# 2_Sheet_2_copy.net
KiCad netlist of a schematic drawn in Altium Designer
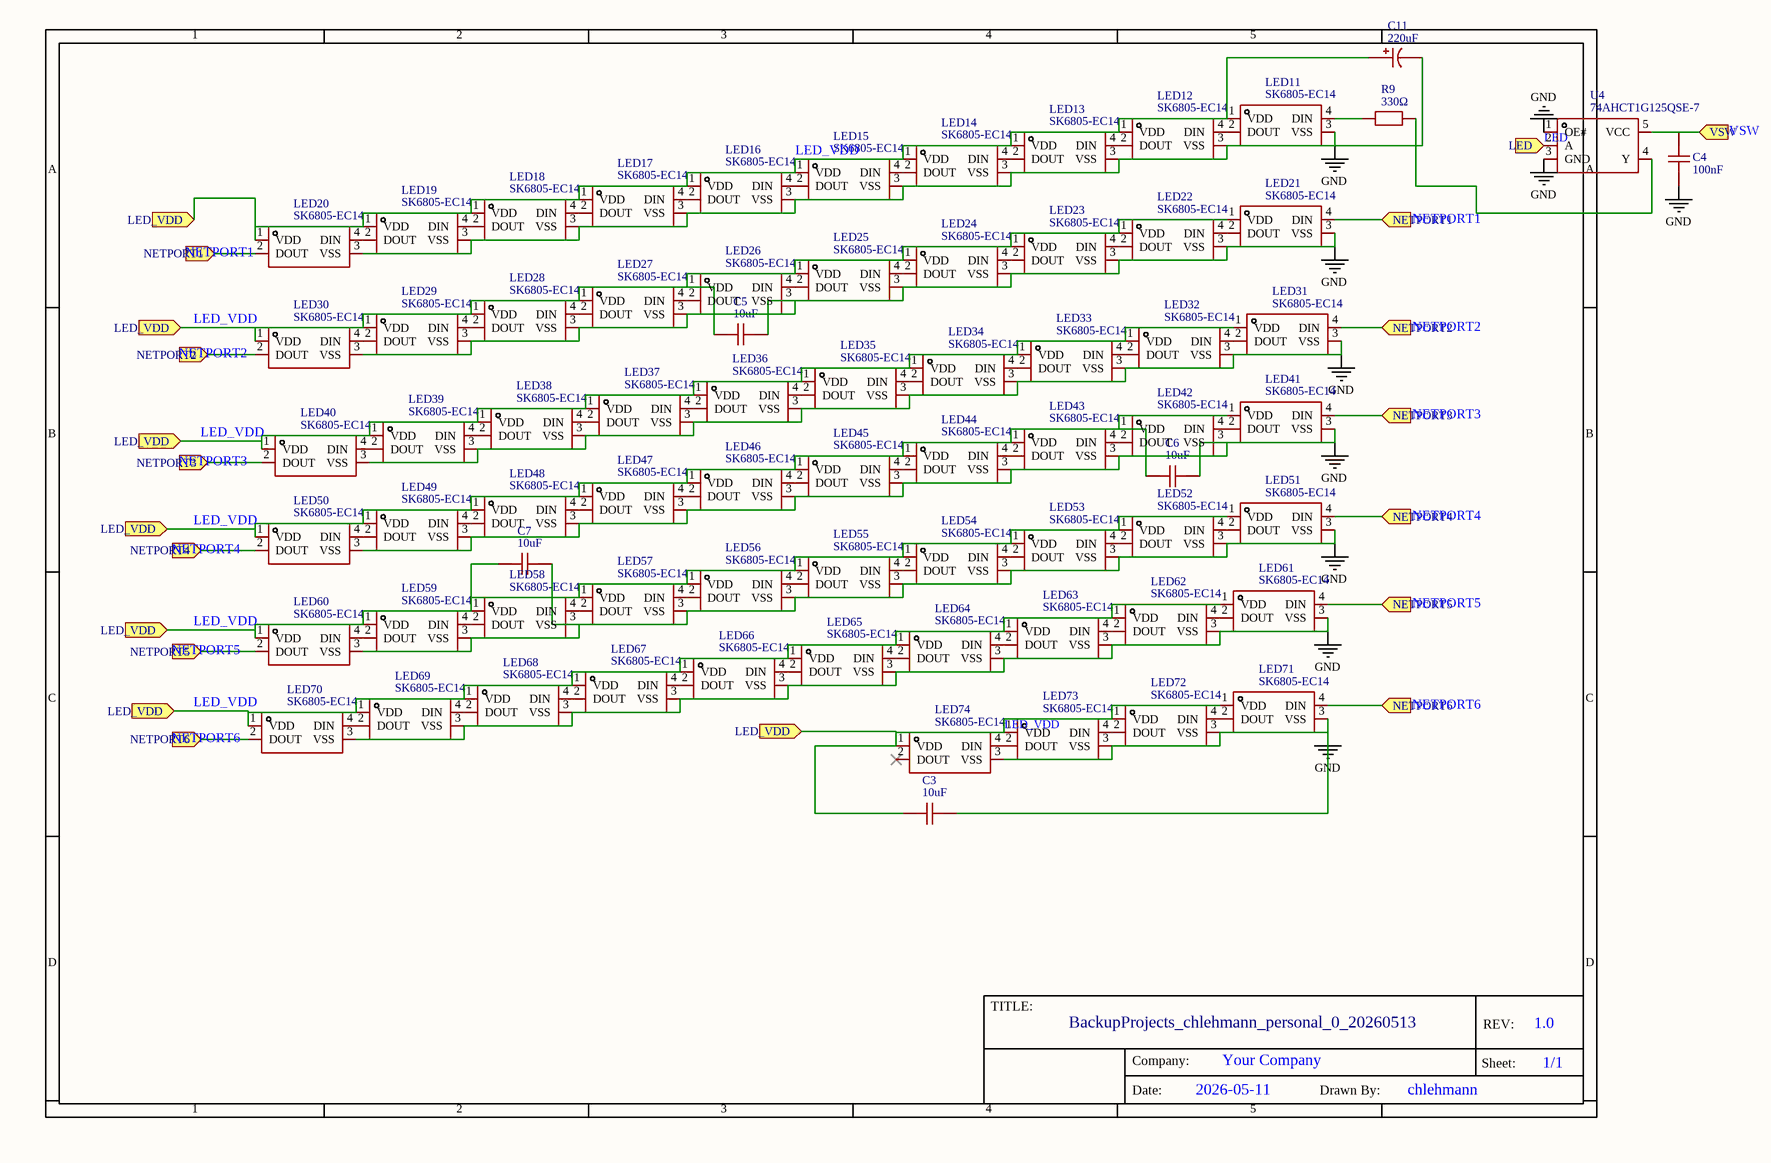
[diagram p0: 2_Sheet_2 copy.schdoc]

(export (version "E")
  (design (tool "Eeschema 10.0.6"))
  (components
    (comp (ref "C3")
      (value "10uF")
      (footprint "C0603")
      (fields
        (field (name "MANUFACTURER") "SAMSUNG(三星)")
        (field (name "MANUFACTURER PART") "CL10A106KP8NNNC")
      )
      (libsource (lib "altium-import") (part "root_0_10uF_"))
    )
    (comp (ref "C4")
      (value "100nF")
      (footprint "C0603")
      (fields
        (field (name "MANUFACTURER") "HRE(芯声)")
        (field (name "MANUFACTURER PART") "CGA0603X7R104K250JT")
        (field (name "CONTRIBUTOR") "lcsc")
      )
      (libsource (lib "altium-import") (part "root_1_100nF_"))
    )
    (comp (ref "C5")
      (value "10uF")
      (footprint "C0603")
      (fields
        (field (name "MANUFACTURER") "SAMSUNG(三星)")
        (field (name "MANUFACTURER PART") "CL10A106KP8NNNC")
      )
      (libsource (lib "altium-import") (part "root_0_10uF_"))
    )
    (comp (ref "C6")
      (value "10uF")
      (footprint "C0603")
      (fields
        (field (name "MANUFACTURER") "SAMSUNG(三星)")
        (field (name "MANUFACTURER PART") "CL10A106KP8NNNC")
      )
      (libsource (lib "altium-import") (part "root_0_10uF_"))
    )
    (comp (ref "C7")
      (value "10uF")
      (footprint "C0603")
      (fields
        (field (name "MANUFACTURER") "SAMSUNG(三星)")
        (field (name "MANUFACTURER PART") "CL10A106KP8NNNC")
      )
      (libsource (lib "altium-import") (part "root_0_10uF_"))
    )
    (comp (ref "C11")
      (value "220uF")
      (footprint "CAP-SMD_BD6.3-L6.6-W6.6-LS7.2-FD")
      (fields
        (field (name "MANUFACTURER") "KNSCHA(科尼盛)")
        (field (name "MANUFACTURER PART") "RVT220UF6.3V67RV0014")
        (field (name "CONTRIBUTOR") "LCSC")
      )
      (libsource (lib "altium-import") (part "root_0_220uF_"))
    )
    (comp (ref "LED11")
      (value "SK6805-EC14")
      (footprint "LED-SMD_4P-L1.4-W1.4-TL")
      (fields (field (name "MANUFACTURER") "欧思科光电"))
      (libsource (lib "altium-import") (part "root_0_SK6805-EC14_C2909055_"))
    )
    (comp (ref "LED12")
      (value "SK6805-EC14")
      (footprint "LED-SMD_4P-L1.4-W1.4-TL")
      (fields (field (name "MANUFACTURER") "欧思科光电"))
      (libsource (lib "altium-import") (part "root_0_SK6805-EC14_C2909055_"))
    )
    (comp (ref "LED13")
      (value "SK6805-EC14")
      (footprint "LED-SMD_4P-L1.4-W1.4-TL")
      (fields (field (name "MANUFACTURER") "欧思科光电"))
      (libsource (lib "altium-import") (part "root_0_SK6805-EC14_C2909055_"))
    )
    (comp (ref "LED14")
      (value "SK6805-EC14")
      (footprint "LED-SMD_4P-L1.4-W1.4-TL")
      (fields (field (name "MANUFACTURER") "欧思科光电"))
      (libsource (lib "altium-import") (part "root_0_SK6805-EC14_C2909055_"))
    )
    (comp (ref "LED15")
      (value "SK6805-EC14")
      (footprint "LED-SMD_4P-L1.4-W1.4-TL")
      (fields (field (name "MANUFACTURER") "欧思科光电"))
      (libsource (lib "altium-import") (part "root_0_SK6805-EC14_C2909055_"))
    )
    (comp (ref "LED16")
      (value "SK6805-EC14")
      (footprint "LED-SMD_4P-L1.4-W1.4-TL")
      (fields (field (name "MANUFACTURER") "欧思科光电"))
      (libsource (lib "altium-import") (part "root_0_SK6805-EC14_C2909055_"))
    )
    (comp (ref "LED17")
      (value "SK6805-EC14")
      (footprint "LED-SMD_4P-L1.4-W1.4-TL")
      (fields (field (name "MANUFACTURER") "欧思科光电"))
      (libsource (lib "altium-import") (part "root_0_SK6805-EC14_C2909055_"))
    )
    (comp (ref "LED18")
      (value "SK6805-EC14")
      (footprint "LED-SMD_4P-L1.4-W1.4-TL")
      (fields (field (name "MANUFACTURER") "欧思科光电"))
      (libsource (lib "altium-import") (part "root_0_SK6805-EC14_C2909055_"))
    )
    (comp (ref "LED19")
      (value "SK6805-EC14")
      (footprint "LED-SMD_4P-L1.4-W1.4-TL")
      (fields (field (name "MANUFACTURER") "欧思科光电"))
      (libsource (lib "altium-import") (part "root_0_SK6805-EC14_C2909055_"))
    )
    (comp (ref "LED20")
      (value "SK6805-EC14")
      (footprint "LED-SMD_4P-L1.4-W1.4-TL")
      (fields (field (name "MANUFACTURER") "欧思科光电"))
      (libsource (lib "altium-import") (part "root_0_SK6805-EC14_C2909055_"))
    )
    (comp (ref "LED21")
      (value "SK6805-EC14")
      (footprint "LED-SMD_4P-L1.4-W1.4-TL")
      (fields (field (name "MANUFACTURER") "欧思科光电"))
      (libsource (lib "altium-import") (part "root_0_SK6805-EC14_C2909055_"))
    )
    (comp (ref "LED22")
      (value "SK6805-EC14")
      (footprint "LED-SMD_4P-L1.4-W1.4-TL")
      (fields (field (name "MANUFACTURER") "欧思科光电"))
      (libsource (lib "altium-import") (part "root_0_SK6805-EC14_C2909055_"))
    )
    (comp (ref "LED23")
      (value "SK6805-EC14")
      (footprint "LED-SMD_4P-L1.4-W1.4-TL")
      (fields (field (name "MANUFACTURER") "欧思科光电"))
      (libsource (lib "altium-import") (part "root_0_SK6805-EC14_C2909055_"))
    )
    (comp (ref "LED24")
      (value "SK6805-EC14")
      (footprint "LED-SMD_4P-L1.4-W1.4-TL")
      (fields (field (name "MANUFACTURER") "欧思科光电"))
      (libsource (lib "altium-import") (part "root_0_SK6805-EC14_C2909055_"))
    )
    (comp (ref "LED25")
      (value "SK6805-EC14")
      (footprint "LED-SMD_4P-L1.4-W1.4-TL")
      (fields (field (name "MANUFACTURER") "欧思科光电"))
      (libsource (lib "altium-import") (part "root_0_SK6805-EC14_C2909055_"))
    )
    (comp (ref "LED26")
      (value "SK6805-EC14")
      (footprint "LED-SMD_4P-L1.4-W1.4-TL")
      (fields (field (name "MANUFACTURER") "欧思科光电"))
      (libsource (lib "altium-import") (part "root_0_SK6805-EC14_C2909055_"))
    )
    (comp (ref "LED27")
      (value "SK6805-EC14")
      (footprint "LED-SMD_4P-L1.4-W1.4-TL")
      (fields (field (name "MANUFACTURER") "欧思科光电"))
      (libsource (lib "altium-import") (part "root_0_SK6805-EC14_C2909055_"))
    )
    (comp (ref "LED28")
      (value "SK6805-EC14")
      (footprint "LED-SMD_4P-L1.4-W1.4-TL")
      (fields (field (name "MANUFACTURER") "欧思科光电"))
      (libsource (lib "altium-import") (part "root_0_SK6805-EC14_C2909055_"))
    )
    (comp (ref "LED29")
      (value "SK6805-EC14")
      (footprint "LED-SMD_4P-L1.4-W1.4-TL")
      (fields (field (name "MANUFACTURER") "欧思科光电"))
      (libsource (lib "altium-import") (part "root_0_SK6805-EC14_C2909055_"))
    )
    (comp (ref "LED30")
      (value "SK6805-EC14")
      (footprint "LED-SMD_4P-L1.4-W1.4-TL")
      (fields (field (name "MANUFACTURER") "欧思科光电"))
      (libsource (lib "altium-import") (part "root_0_SK6805-EC14_C2909055_"))
    )
    (comp (ref "LED31")
      (value "SK6805-EC14")
      (footprint "LED-SMD_4P-L1.4-W1.4-TL")
      (fields (field (name "MANUFACTURER") "欧思科光电"))
      (libsource (lib "altium-import") (part "root_0_SK6805-EC14_C2909055_"))
    )
    (comp (ref "LED32")
      (value "SK6805-EC14")
      (footprint "LED-SMD_4P-L1.4-W1.4-TL")
      (fields (field (name "MANUFACTURER") "欧思科光电"))
      (libsource (lib "altium-import") (part "root_0_SK6805-EC14_C2909055_"))
    )
    (comp (ref "LED33")
      (value "SK6805-EC14")
      (footprint "LED-SMD_4P-L1.4-W1.4-TL")
      (fields (field (name "MANUFACTURER") "欧思科光电"))
      (libsource (lib "altium-import") (part "root_0_SK6805-EC14_C2909055_"))
    )
    (comp (ref "LED34")
      (value "SK6805-EC14")
      (footprint "LED-SMD_4P-L1.4-W1.4-TL")
      (fields (field (name "MANUFACTURER") "欧思科光电"))
      (libsource (lib "altium-import") (part "root_0_SK6805-EC14_C2909055_"))
    )
    (comp (ref "LED35")
      (value "SK6805-EC14")
      (footprint "LED-SMD_4P-L1.4-W1.4-TL")
      (fields (field (name "MANUFACTURER") "欧思科光电"))
      (libsource (lib "altium-import") (part "root_0_SK6805-EC14_C2909055_"))
    )
    (comp (ref "LED36")
      (value "SK6805-EC14")
      (footprint "LED-SMD_4P-L1.4-W1.4-TL")
      (fields (field (name "MANUFACTURER") "欧思科光电"))
      (libsource (lib "altium-import") (part "root_0_SK6805-EC14_C2909055_"))
    )
    (comp (ref "LED37")
      (value "SK6805-EC14")
      (footprint "LED-SMD_4P-L1.4-W1.4-TL")
      (fields (field (name "MANUFACTURER") "欧思科光电"))
      (libsource (lib "altium-import") (part "root_0_SK6805-EC14_C2909055_"))
    )
    (comp (ref "LED38")
      (value "SK6805-EC14")
      (footprint "LED-SMD_4P-L1.4-W1.4-TL")
      (fields (field (name "MANUFACTURER") "欧思科光电"))
      (libsource (lib "altium-import") (part "root_0_SK6805-EC14_C2909055_"))
    )
    (comp (ref "LED39")
      (value "SK6805-EC14")
      (footprint "LED-SMD_4P-L1.4-W1.4-TL")
      (fields (field (name "MANUFACTURER") "欧思科光电"))
      (libsource (lib "altium-import") (part "root_0_SK6805-EC14_C2909055_"))
    )
    (comp (ref "LED40")
      (value "SK6805-EC14")
      (footprint "LED-SMD_4P-L1.4-W1.4-TL")
      (fields (field (name "MANUFACTURER") "欧思科光电"))
      (libsource (lib "altium-import") (part "root_0_SK6805-EC14_C2909055_"))
    )
    (comp (ref "LED41")
      (value "SK6805-EC14")
      (footprint "LED-SMD_4P-L1.4-W1.4-TL")
      (fields (field (name "MANUFACTURER") "欧思科光电"))
      (libsource (lib "altium-import") (part "root_0_SK6805-EC14_C2909055_"))
    )
    (comp (ref "LED42")
      (value "SK6805-EC14")
      (footprint "LED-SMD_4P-L1.4-W1.4-TL")
      (fields (field (name "MANUFACTURER") "欧思科光电"))
      (libsource (lib "altium-import") (part "root_0_SK6805-EC14_C2909055_"))
    )
    (comp (ref "LED43")
      (value "SK6805-EC14")
      (footprint "LED-SMD_4P-L1.4-W1.4-TL")
      (fields (field (name "MANUFACTURER") "欧思科光电"))
      (libsource (lib "altium-import") (part "root_0_SK6805-EC14_C2909055_"))
    )
    (comp (ref "LED44")
      (value "SK6805-EC14")
      (footprint "LED-SMD_4P-L1.4-W1.4-TL")
      (fields (field (name "MANUFACTURER") "欧思科光电"))
      (libsource (lib "altium-import") (part "root_0_SK6805-EC14_C2909055_"))
    )
    (comp (ref "LED45")
      (value "SK6805-EC14")
      (footprint "LED-SMD_4P-L1.4-W1.4-TL")
      (fields (field (name "MANUFACTURER") "欧思科光电"))
      (libsource (lib "altium-import") (part "root_0_SK6805-EC14_C2909055_"))
    )
    (comp (ref "LED46")
      (value "SK6805-EC14")
      (footprint "LED-SMD_4P-L1.4-W1.4-TL")
      (fields (field (name "MANUFACTURER") "欧思科光电"))
      (libsource (lib "altium-import") (part "root_0_SK6805-EC14_C2909055_"))
    )
    (comp (ref "LED47")
      (value "SK6805-EC14")
      (footprint "LED-SMD_4P-L1.4-W1.4-TL")
      (fields (field (name "MANUFACTURER") "欧思科光电"))
      (libsource (lib "altium-import") (part "root_0_SK6805-EC14_C2909055_"))
    )
    (comp (ref "LED48")
      (value "SK6805-EC14")
      (footprint "LED-SMD_4P-L1.4-W1.4-TL")
      (fields (field (name "MANUFACTURER") "欧思科光电"))
      (libsource (lib "altium-import") (part "root_0_SK6805-EC14_C2909055_"))
    )
    (comp (ref "LED49")
      (value "SK6805-EC14")
      (footprint "LED-SMD_4P-L1.4-W1.4-TL")
      (fields (field (name "MANUFACTURER") "欧思科光电"))
      (libsource (lib "altium-import") (part "root_0_SK6805-EC14_C2909055_"))
    )
    (comp (ref "LED50")
      (value "SK6805-EC14")
      (footprint "LED-SMD_4P-L1.4-W1.4-TL")
      (fields (field (name "MANUFACTURER") "欧思科光电"))
      (libsource (lib "altium-import") (part "root_0_SK6805-EC14_C2909055_"))
    )
    (comp (ref "LED51")
      (value "SK6805-EC14")
      (footprint "LED-SMD_4P-L1.4-W1.4-TL")
      (fields (field (name "MANUFACTURER") "欧思科光电"))
      (libsource (lib "altium-import") (part "root_0_SK6805-EC14_C2909055_"))
    )
    (comp (ref "LED52")
      (value "SK6805-EC14")
      (footprint "LED-SMD_4P-L1.4-W1.4-TL")
      (fields (field (name "MANUFACTURER") "欧思科光电"))
      (libsource (lib "altium-import") (part "root_0_SK6805-EC14_C2909055_"))
    )
    (comp (ref "LED53")
      (value "SK6805-EC14")
      (footprint "LED-SMD_4P-L1.4-W1.4-TL")
      (fields (field (name "MANUFACTURER") "欧思科光电"))
      (libsource (lib "altium-import") (part "root_0_SK6805-EC14_C2909055_"))
    )
    (comp (ref "LED54")
      (value "SK6805-EC14")
      (footprint "LED-SMD_4P-L1.4-W1.4-TL")
      (fields (field (name "MANUFACTURER") "欧思科光电"))
      (libsource (lib "altium-import") (part "root_0_SK6805-EC14_C2909055_"))
    )
    (comp (ref "LED55")
      (value "SK6805-EC14")
      (footprint "LED-SMD_4P-L1.4-W1.4-TL")
      (fields (field (name "MANUFACTURER") "欧思科光电"))
      (libsource (lib "altium-import") (part "root_0_SK6805-EC14_C2909055_"))
    )
    (comp (ref "LED56")
      (value "SK6805-EC14")
      (footprint "LED-SMD_4P-L1.4-W1.4-TL")
      (fields (field (name "MANUFACTURER") "欧思科光电"))
      (libsource (lib "altium-import") (part "root_0_SK6805-EC14_C2909055_"))
    )
    (comp (ref "LED57")
      (value "SK6805-EC14")
      (footprint "LED-SMD_4P-L1.4-W1.4-TL")
      (fields (field (name "MANUFACTURER") "欧思科光电"))
      (libsource (lib "altium-import") (part "root_0_SK6805-EC14_C2909055_"))
    )
    (comp (ref "LED58")
      (value "SK6805-EC14")
      (footprint "LED-SMD_4P-L1.4-W1.4-TL")
      (fields (field (name "MANUFACTURER") "欧思科光电"))
      (libsource (lib "altium-import") (part "root_0_SK6805-EC14_C2909055_"))
    )
    (comp (ref "LED59")
      (value "SK6805-EC14")
      (footprint "LED-SMD_4P-L1.4-W1.4-TL")
      (fields (field (name "MANUFACTURER") "欧思科光电"))
      (libsource (lib "altium-import") (part "root_0_SK6805-EC14_C2909055_"))
    )
    (comp (ref "LED60")
      (value "SK6805-EC14")
      (footprint "LED-SMD_4P-L1.4-W1.4-TL")
      (fields (field (name "MANUFACTURER") "欧思科光电"))
      (libsource (lib "altium-import") (part "root_0_SK6805-EC14_C2909055_"))
    )
    (comp (ref "LED61")
      (value "SK6805-EC14")
      (footprint "LED-SMD_4P-L1.4-W1.4-TL")
      (fields (field (name "MANUFACTURER") "欧思科光电"))
      (libsource (lib "altium-import") (part "root_0_SK6805-EC14_C2909055_"))
    )
    (comp (ref "LED62")
      (value "SK6805-EC14")
      (footprint "LED-SMD_4P-L1.4-W1.4-TL")
      (fields (field (name "MANUFACTURER") "欧思科光电"))
      (libsource (lib "altium-import") (part "root_0_SK6805-EC14_C2909055_"))
    )
    (comp (ref "LED63")
      (value "SK6805-EC14")
      (footprint "LED-SMD_4P-L1.4-W1.4-TL")
      (fields (field (name "MANUFACTURER") "欧思科光电"))
      (libsource (lib "altium-import") (part "root_0_SK6805-EC14_C2909055_"))
    )
    (comp (ref "LED64")
      (value "SK6805-EC14")
      (footprint "LED-SMD_4P-L1.4-W1.4-TL")
      (fields (field (name "MANUFACTURER") "欧思科光电"))
      (libsource (lib "altium-import") (part "root_0_SK6805-EC14_C2909055_"))
    )
    (comp (ref "LED65")
      (value "SK6805-EC14")
      (footprint "LED-SMD_4P-L1.4-W1.4-TL")
      (fields (field (name "MANUFACTURER") "欧思科光电"))
      (libsource (lib "altium-import") (part "root_0_SK6805-EC14_C2909055_"))
    )
    (comp (ref "LED66")
      (value "SK6805-EC14")
      (footprint "LED-SMD_4P-L1.4-W1.4-TL")
      (fields (field (name "MANUFACTURER") "欧思科光电"))
      (libsource (lib "altium-import") (part "root_0_SK6805-EC14_C2909055_"))
    )
    (comp (ref "LED67")
      (value "SK6805-EC14")
      (footprint "LED-SMD_4P-L1.4-W1.4-TL")
      (fields (field (name "MANUFACTURER") "欧思科光电"))
      (libsource (lib "altium-import") (part "root_0_SK6805-EC14_C2909055_"))
    )
    (comp (ref "LED68")
      (value "SK6805-EC14")
      (footprint "LED-SMD_4P-L1.4-W1.4-TL")
      (fields (field (name "MANUFACTURER") "欧思科光电"))
      (libsource (lib "altium-import") (part "root_0_SK6805-EC14_C2909055_"))
    )
    (comp (ref "LED69")
      (value "SK6805-EC14")
      (footprint "LED-SMD_4P-L1.4-W1.4-TL")
      (fields (field (name "MANUFACTURER") "欧思科光电"))
      (libsource (lib "altium-import") (part "root_0_SK6805-EC14_C2909055_"))
    )
    (comp (ref "LED70")
      (value "SK6805-EC14")
      (footprint "LED-SMD_4P-L1.4-W1.4-TL")
      (fields (field (name "MANUFACTURER") "欧思科光电"))
      (libsource (lib "altium-import") (part "root_0_SK6805-EC14_C2909055_"))
    )
    (comp (ref "LED71")
      (value "SK6805-EC14")
      (footprint "LED-SMD_4P-L1.4-W1.4-TL")
      (fields (field (name "MANUFACTURER") "欧思科光电"))
      (libsource (lib "altium-import") (part "root_0_SK6805-EC14_C2909055_"))
    )
    (comp (ref "LED72")
      (value "SK6805-EC14")
      (footprint "LED-SMD_4P-L1.4-W1.4-TL")
      (fields (field (name "MANUFACTURER") "欧思科光电"))
      (libsource (lib "altium-import") (part "root_0_SK6805-EC14_C2909055_"))
    )
    (comp (ref "LED73")
      (value "SK6805-EC14")
      (footprint "LED-SMD_4P-L1.4-W1.4-TL")
      (fields (field (name "MANUFACTURER") "欧思科光电"))
      (libsource (lib "altium-import") (part "root_0_SK6805-EC14_C2909055_"))
    )
    (comp (ref "LED74")
      (value "SK6805-EC14")
      (footprint "LED-SMD_4P-L1.4-W1.4-TL")
      (fields (field (name "MANUFACTURER") "欧思科光电"))
      (libsource (lib "altium-import") (part "root_0_SK6805-EC14_C2909055_"))
    )
    (comp (ref "R9")
      (value "330Ω")
      (footprint "R0603")
      (fields
        (field (name "MANUFACTURER") "Viking(光颉)")
        (field (name "MANUFACTURER PART") "AR03BTCX3300")
        (field (name "CONTRIBUTOR") "lcsc")
      )
      (libsource (lib "altium-import") (part "root_0_330Ω_"))
    )
    (comp (ref "U4")
      (value "74AHCT1G125QSE-7")
      (footprint "SOT-353-5_L2.0-W1.3-P0.65-LS2.1-BR")
      (fields (field (name "MANUFACTURER") "DIODES(美台)") (field (name "CONTRIBUTOR") "lcsc"))
      (libsource (lib "altium-import") (part "root_0_74AHCT1G125QSE-7_"))
    )
  )
  (nets
    (net (code "1") (name "/LED") (class "Default")
      (node (ref "U4") (pin "2") (pinfunction "A_2") (pintype "passive"))
    )
    (net (code "2") (name "/LED_VDD") (class "Default")
      (node (ref "C11") (pin "1") (pinfunction "1_1") (pintype "passive"))
      (node (ref "C3") (pin "1") (pinfunction "1_1") (pintype "passive"))
      (node (ref "C5") (pin "1") (pinfunction "1_1") (pintype "passive"))
      (node (ref "C6") (pin "1") (pinfunction "1_1") (pintype "passive"))
      (node (ref "C7") (pin "1") (pinfunction "1_1") (pintype "passive"))
      (node (ref "LED11") (pin "1") (pinfunction "VDD_1") (pintype "passive"))
      (node (ref "LED12") (pin "1") (pinfunction "VDD_1") (pintype "passive"))
      (node (ref "LED13") (pin "1") (pinfunction "VDD_1") (pintype "passive"))
      (node (ref "LED14") (pin "1") (pinfunction "VDD_1") (pintype "passive"))
      (node (ref "LED15") (pin "1") (pinfunction "VDD_1") (pintype "passive"))
      (node (ref "LED16") (pin "1") (pinfunction "VDD_1") (pintype "passive"))
      (node (ref "LED17") (pin "1") (pinfunction "VDD_1") (pintype "passive"))
      (node (ref "LED18") (pin "1") (pinfunction "VDD_1") (pintype "passive"))
      (node (ref "LED19") (pin "1") (pinfunction "VDD_1") (pintype "passive"))
      (node (ref "LED20") (pin "1") (pinfunction "VDD_1") (pintype "passive"))
      (node (ref "LED21") (pin "1") (pinfunction "VDD_1") (pintype "passive"))
      (node (ref "LED22") (pin "1") (pinfunction "VDD_1") (pintype "passive"))
      (node (ref "LED23") (pin "1") (pinfunction "VDD_1") (pintype "passive"))
      (node (ref "LED24") (pin "1") (pinfunction "VDD_1") (pintype "passive"))
      (node (ref "LED25") (pin "1") (pinfunction "VDD_1") (pintype "passive"))
      (node (ref "LED26") (pin "1") (pinfunction "VDD_1") (pintype "passive"))
      (node (ref "LED27") (pin "1") (pinfunction "VDD_1") (pintype "passive"))
      (node (ref "LED28") (pin "1") (pinfunction "VDD_1") (pintype "passive"))
      (node (ref "LED29") (pin "1") (pinfunction "VDD_1") (pintype "passive"))
      (node (ref "LED30") (pin "1") (pinfunction "VDD_1") (pintype "passive"))
      (node (ref "LED31") (pin "1") (pinfunction "VDD_1") (pintype "passive"))
      (node (ref "LED32") (pin "1") (pinfunction "VDD_1") (pintype "passive"))
      (node (ref "LED33") (pin "1") (pinfunction "VDD_1") (pintype "passive"))
      (node (ref "LED34") (pin "1") (pinfunction "VDD_1") (pintype "passive"))
      (node (ref "LED35") (pin "1") (pinfunction "VDD_1") (pintype "passive"))
      (node (ref "LED36") (pin "1") (pinfunction "VDD_1") (pintype "passive"))
      (node (ref "LED37") (pin "1") (pinfunction "VDD_1") (pintype "passive"))
      (node (ref "LED38") (pin "1") (pinfunction "VDD_1") (pintype "passive"))
      (node (ref "LED39") (pin "1") (pinfunction "VDD_1") (pintype "passive"))
      (node (ref "LED40") (pin "1") (pinfunction "VDD_1") (pintype "passive"))
      (node (ref "LED41") (pin "1") (pinfunction "VDD_1") (pintype "passive"))
      (node (ref "LED42") (pin "1") (pinfunction "VDD_1") (pintype "passive"))
      (node (ref "LED43") (pin "1") (pinfunction "VDD_1") (pintype "passive"))
      (node (ref "LED44") (pin "1") (pinfunction "VDD_1") (pintype "passive"))
      (node (ref "LED45") (pin "1") (pinfunction "VDD_1") (pintype "passive"))
      (node (ref "LED46") (pin "1") (pinfunction "VDD_1") (pintype "passive"))
      (node (ref "LED47") (pin "1") (pinfunction "VDD_1") (pintype "passive"))
      (node (ref "LED48") (pin "1") (pinfunction "VDD_1") (pintype "passive"))
      (node (ref "LED49") (pin "1") (pinfunction "VDD_1") (pintype "passive"))
      (node (ref "LED50") (pin "1") (pinfunction "VDD_1") (pintype "passive"))
      (node (ref "LED51") (pin "1") (pinfunction "VDD_1") (pintype "passive"))
      (node (ref "LED52") (pin "1") (pinfunction "VDD_1") (pintype "passive"))
      (node (ref "LED53") (pin "1") (pinfunction "VDD_1") (pintype "passive"))
      (node (ref "LED54") (pin "1") (pinfunction "VDD_1") (pintype "passive"))
      (node (ref "LED55") (pin "1") (pinfunction "VDD_1") (pintype "passive"))
      (node (ref "LED56") (pin "1") (pinfunction "VDD_1") (pintype "passive"))
      (node (ref "LED57") (pin "1") (pinfunction "VDD_1") (pintype "passive"))
      (node (ref "LED58") (pin "1") (pinfunction "VDD_1") (pintype "passive"))
      (node (ref "LED59") (pin "1") (pinfunction "VDD_1") (pintype "passive"))
      (node (ref "LED60") (pin "1") (pinfunction "VDD_1") (pintype "passive"))
      (node (ref "LED61") (pin "1") (pinfunction "VDD_1") (pintype "passive"))
      (node (ref "LED62") (pin "1") (pinfunction "VDD_1") (pintype "passive"))
      (node (ref "LED63") (pin "1") (pinfunction "VDD_1") (pintype "passive"))
      (node (ref "LED64") (pin "1") (pinfunction "VDD_1") (pintype "passive"))
      (node (ref "LED65") (pin "1") (pinfunction "VDD_1") (pintype "passive"))
      (node (ref "LED66") (pin "1") (pinfunction "VDD_1") (pintype "passive"))
      (node (ref "LED67") (pin "1") (pinfunction "VDD_1") (pintype "passive"))
      (node (ref "LED68") (pin "1") (pinfunction "VDD_1") (pintype "passive"))
      (node (ref "LED69") (pin "1") (pinfunction "VDD_1") (pintype "passive"))
      (node (ref "LED70") (pin "1") (pinfunction "VDD_1") (pintype "passive"))
      (node (ref "LED71") (pin "1") (pinfunction "VDD_1") (pintype "passive"))
      (node (ref "LED72") (pin "1") (pinfunction "VDD_1") (pintype "passive"))
      (node (ref "LED73") (pin "1") (pinfunction "VDD_1") (pintype "passive"))
      (node (ref "LED74") (pin "1") (pinfunction "VDD_1") (pintype "passive"))
    )
    (net (code "3") (name "/NETPORT1") (class "Default")
      (node (ref "LED20") (pin "2") (pinfunction "DOUT_2") (pintype "passive"))
      (node (ref "LED21") (pin "4") (pinfunction "DIN_4") (pintype "passive"))
    )
    (net (code "4") (name "/NETPORT2") (class "Default")
      (node (ref "LED30") (pin "2") (pinfunction "DOUT_2") (pintype "passive"))
      (node (ref "LED31") (pin "4") (pinfunction "DIN_4") (pintype "passive"))
    )
    (net (code "5") (name "/NETPORT3") (class "Default")
      (node (ref "LED40") (pin "2") (pinfunction "DOUT_2") (pintype "passive"))
      (node (ref "LED41") (pin "4") (pinfunction "DIN_4") (pintype "passive"))
    )
    (net (code "6") (name "/NETPORT4") (class "Default")
      (node (ref "LED50") (pin "2") (pinfunction "DOUT_2") (pintype "passive"))
      (node (ref "LED51") (pin "4") (pinfunction "DIN_4") (pintype "passive"))
    )
    (net (code "7") (name "/NETPORT5") (class "Default")
      (node (ref "LED60") (pin "2") (pinfunction "DOUT_2") (pintype "passive"))
      (node (ref "LED61") (pin "4") (pinfunction "DIN_4") (pintype "passive"))
    )
    (net (code "8") (name "/NETPORT6") (class "Default")
      (node (ref "LED70") (pin "2") (pinfunction "DOUT_2") (pintype "passive"))
      (node (ref "LED71") (pin "4") (pinfunction "DIN_4") (pintype "passive"))
    )
    (net (code "9") (name "/VSW") (class "Default")
      (node (ref "C4") (pin "2") (pinfunction "2_2") (pintype "passive"))
      (node (ref "U4") (pin "5") (pinfunction "VCC_5") (pintype "passive"))
    )
    (net (code "10") (name "GND") (class "Default")
      (node (ref "C11") (pin "2") (pinfunction "2_2") (pintype "passive"))
      (node (ref "C3") (pin "2") (pinfunction "2_2") (pintype "passive"))
      (node (ref "C4") (pin "1") (pinfunction "1_1") (pintype "passive"))
      (node (ref "C5") (pin "2") (pinfunction "2_2") (pintype "passive"))
      (node (ref "C6") (pin "2") (pinfunction "2_2") (pintype "passive"))
      (node (ref "C7") (pin "2") (pinfunction "2_2") (pintype "passive"))
      (node (ref "LED11") (pin "3") (pinfunction "VSS_3") (pintype "passive"))
      (node (ref "LED12") (pin "3") (pinfunction "VSS_3") (pintype "passive"))
      (node (ref "LED13") (pin "3") (pinfunction "VSS_3") (pintype "passive"))
      (node (ref "LED14") (pin "3") (pinfunction "VSS_3") (pintype "passive"))
      (node (ref "LED15") (pin "3") (pinfunction "VSS_3") (pintype "passive"))
      (node (ref "LED16") (pin "3") (pinfunction "VSS_3") (pintype "passive"))
      (node (ref "LED17") (pin "3") (pinfunction "VSS_3") (pintype "passive"))
      (node (ref "LED18") (pin "3") (pinfunction "VSS_3") (pintype "passive"))
      (node (ref "LED19") (pin "3") (pinfunction "VSS_3") (pintype "passive"))
      (node (ref "LED20") (pin "3") (pinfunction "VSS_3") (pintype "passive"))
      (node (ref "LED21") (pin "3") (pinfunction "VSS_3") (pintype "passive"))
      (node (ref "LED22") (pin "3") (pinfunction "VSS_3") (pintype "passive"))
      (node (ref "LED23") (pin "3") (pinfunction "VSS_3") (pintype "passive"))
      (node (ref "LED24") (pin "3") (pinfunction "VSS_3") (pintype "passive"))
      (node (ref "LED25") (pin "3") (pinfunction "VSS_3") (pintype "passive"))
      (node (ref "LED26") (pin "3") (pinfunction "VSS_3") (pintype "passive"))
      (node (ref "LED27") (pin "3") (pinfunction "VSS_3") (pintype "passive"))
      (node (ref "LED28") (pin "3") (pinfunction "VSS_3") (pintype "passive"))
      (node (ref "LED29") (pin "3") (pinfunction "VSS_3") (pintype "passive"))
      (node (ref "LED30") (pin "3") (pinfunction "VSS_3") (pintype "passive"))
      (node (ref "LED31") (pin "3") (pinfunction "VSS_3") (pintype "passive"))
      (node (ref "LED32") (pin "3") (pinfunction "VSS_3") (pintype "passive"))
      (node (ref "LED33") (pin "3") (pinfunction "VSS_3") (pintype "passive"))
      (node (ref "LED34") (pin "3") (pinfunction "VSS_3") (pintype "passive"))
      (node (ref "LED35") (pin "3") (pinfunction "VSS_3") (pintype "passive"))
      (node (ref "LED36") (pin "3") (pinfunction "VSS_3") (pintype "passive"))
      (node (ref "LED37") (pin "3") (pinfunction "VSS_3") (pintype "passive"))
      (node (ref "LED38") (pin "3") (pinfunction "VSS_3") (pintype "passive"))
      (node (ref "LED39") (pin "3") (pinfunction "VSS_3") (pintype "passive"))
      (node (ref "LED40") (pin "3") (pinfunction "VSS_3") (pintype "passive"))
      (node (ref "LED41") (pin "3") (pinfunction "VSS_3") (pintype "passive"))
      (node (ref "LED42") (pin "3") (pinfunction "VSS_3") (pintype "passive"))
      (node (ref "LED43") (pin "3") (pinfunction "VSS_3") (pintype "passive"))
      (node (ref "LED44") (pin "3") (pinfunction "VSS_3") (pintype "passive"))
      (node (ref "LED45") (pin "3") (pinfunction "VSS_3") (pintype "passive"))
      (node (ref "LED46") (pin "3") (pinfunction "VSS_3") (pintype "passive"))
      (node (ref "LED47") (pin "3") (pinfunction "VSS_3") (pintype "passive"))
      (node (ref "LED48") (pin "3") (pinfunction "VSS_3") (pintype "passive"))
      (node (ref "LED49") (pin "3") (pinfunction "VSS_3") (pintype "passive"))
      (node (ref "LED50") (pin "3") (pinfunction "VSS_3") (pintype "passive"))
      (node (ref "LED51") (pin "3") (pinfunction "VSS_3") (pintype "passive"))
      (node (ref "LED52") (pin "3") (pinfunction "VSS_3") (pintype "passive"))
      (node (ref "LED53") (pin "3") (pinfunction "VSS_3") (pintype "passive"))
      (node (ref "LED54") (pin "3") (pinfunction "VSS_3") (pintype "passive"))
      (node (ref "LED55") (pin "3") (pinfunction "VSS_3") (pintype "passive"))
      (node (ref "LED56") (pin "3") (pinfunction "VSS_3") (pintype "passive"))
      (node (ref "LED57") (pin "3") (pinfunction "VSS_3") (pintype "passive"))
      (node (ref "LED58") (pin "3") (pinfunction "VSS_3") (pintype "passive"))
      (node (ref "LED59") (pin "3") (pinfunction "VSS_3") (pintype "passive"))
      (node (ref "LED60") (pin "3") (pinfunction "VSS_3") (pintype "passive"))
      (node (ref "LED61") (pin "3") (pinfunction "VSS_3") (pintype "passive"))
      (node (ref "LED62") (pin "3") (pinfunction "VSS_3") (pintype "passive"))
      (node (ref "LED63") (pin "3") (pinfunction "VSS_3") (pintype "passive"))
      (node (ref "LED64") (pin "3") (pinfunction "VSS_3") (pintype "passive"))
      (node (ref "LED65") (pin "3") (pinfunction "VSS_3") (pintype "passive"))
      (node (ref "LED66") (pin "3") (pinfunction "VSS_3") (pintype "passive"))
      (node (ref "LED67") (pin "3") (pinfunction "VSS_3") (pintype "passive"))
      (node (ref "LED68") (pin "3") (pinfunction "VSS_3") (pintype "passive"))
      (node (ref "LED69") (pin "3") (pinfunction "VSS_3") (pintype "passive"))
      (node (ref "LED70") (pin "3") (pinfunction "VSS_3") (pintype "passive"))
      (node (ref "LED71") (pin "3") (pinfunction "VSS_3") (pintype "passive"))
      (node (ref "LED72") (pin "3") (pinfunction "VSS_3") (pintype "passive"))
      (node (ref "LED73") (pin "3") (pinfunction "VSS_3") (pintype "passive"))
      (node (ref "LED74") (pin "3") (pinfunction "VSS_3") (pintype "passive"))
      (node (ref "U4") (pin "1") (pinfunction "OE#_1") (pintype "passive"))
      (node (ref "U4") (pin "3") (pinfunction "GND_3") (pintype "passive"))
    )
    (net (code "11") (name "Net-(LED11-DIN)") (class "Default")
      (node (ref "LED11") (pin "4") (pinfunction "DIN_4") (pintype "passive"))
      (node (ref "R9") (pin "1") (pinfunction "1_1") (pintype "passive"))
    )
    (net (code "12") (name "Net-(LED11-DOUT)") (class "Default")
      (node (ref "LED11") (pin "2") (pinfunction "DOUT_2") (pintype "passive"))
      (node (ref "LED12") (pin "4") (pinfunction "DIN_4") (pintype "passive"))
    )
    (net (code "13") (name "Net-(LED12-DOUT)") (class "Default")
      (node (ref "LED12") (pin "2") (pinfunction "DOUT_2") (pintype "passive"))
      (node (ref "LED13") (pin "4") (pinfunction "DIN_4") (pintype "passive"))
    )
    (net (code "14") (name "Net-(LED13-DOUT)") (class "Default")
      (node (ref "LED13") (pin "2") (pinfunction "DOUT_2") (pintype "passive"))
      (node (ref "LED14") (pin "4") (pinfunction "DIN_4") (pintype "passive"))
    )
    (net (code "15") (name "Net-(LED14-DOUT)") (class "Default")
      (node (ref "LED14") (pin "2") (pinfunction "DOUT_2") (pintype "passive"))
      (node (ref "LED15") (pin "4") (pinfunction "DIN_4") (pintype "passive"))
    )
    (net (code "16") (name "Net-(LED15-DOUT)") (class "Default")
      (node (ref "LED15") (pin "2") (pinfunction "DOUT_2") (pintype "passive"))
      (node (ref "LED16") (pin "4") (pinfunction "DIN_4") (pintype "passive"))
    )
    (net (code "17") (name "Net-(LED16-DOUT)") (class "Default")
      (node (ref "LED16") (pin "2") (pinfunction "DOUT_2") (pintype "passive"))
      (node (ref "LED17") (pin "4") (pinfunction "DIN_4") (pintype "passive"))
    )
    (net (code "18") (name "Net-(LED17-DOUT)") (class "Default")
      (node (ref "LED17") (pin "2") (pinfunction "DOUT_2") (pintype "passive"))
      (node (ref "LED18") (pin "4") (pinfunction "DIN_4") (pintype "passive"))
    )
    (net (code "19") (name "Net-(LED18-DOUT)") (class "Default")
      (node (ref "LED18") (pin "2") (pinfunction "DOUT_2") (pintype "passive"))
      (node (ref "LED19") (pin "4") (pinfunction "DIN_4") (pintype "passive"))
    )
    (net (code "20") (name "Net-(LED19-DOUT)") (class "Default")
      (node (ref "LED19") (pin "2") (pinfunction "DOUT_2") (pintype "passive"))
      (node (ref "LED20") (pin "4") (pinfunction "DIN_4") (pintype "passive"))
    )
    (net (code "21") (name "Net-(LED21-DOUT)") (class "Default")
      (node (ref "LED21") (pin "2") (pinfunction "DOUT_2") (pintype "passive"))
      (node (ref "LED22") (pin "4") (pinfunction "DIN_4") (pintype "passive"))
    )
    (net (code "22") (name "Net-(LED22-DOUT)") (class "Default")
      (node (ref "LED22") (pin "2") (pinfunction "DOUT_2") (pintype "passive"))
      (node (ref "LED23") (pin "4") (pinfunction "DIN_4") (pintype "passive"))
    )
    (net (code "23") (name "Net-(LED23-DOUT)") (class "Default")
      (node (ref "LED23") (pin "2") (pinfunction "DOUT_2") (pintype "passive"))
      (node (ref "LED24") (pin "4") (pinfunction "DIN_4") (pintype "passive"))
    )
    (net (code "24") (name "Net-(LED24-DOUT)") (class "Default")
      (node (ref "LED24") (pin "2") (pinfunction "DOUT_2") (pintype "passive"))
      (node (ref "LED25") (pin "4") (pinfunction "DIN_4") (pintype "passive"))
    )
    (net (code "25") (name "Net-(LED25-DOUT)") (class "Default")
      (node (ref "LED25") (pin "2") (pinfunction "DOUT_2") (pintype "passive"))
      (node (ref "LED26") (pin "4") (pinfunction "DIN_4") (pintype "passive"))
    )
    (net (code "26") (name "Net-(LED26-DOUT)") (class "Default")
      (node (ref "LED26") (pin "2") (pinfunction "DOUT_2") (pintype "passive"))
      (node (ref "LED27") (pin "4") (pinfunction "DIN_4") (pintype "passive"))
    )
    (net (code "27") (name "Net-(LED27-DOUT)") (class "Default")
      (node (ref "LED27") (pin "2") (pinfunction "DOUT_2") (pintype "passive"))
      (node (ref "LED28") (pin "4") (pinfunction "DIN_4") (pintype "passive"))
    )
    (net (code "28") (name "Net-(LED28-DOUT)") (class "Default")
      (node (ref "LED28") (pin "2") (pinfunction "DOUT_2") (pintype "passive"))
      (node (ref "LED29") (pin "4") (pinfunction "DIN_4") (pintype "passive"))
    )
    (net (code "29") (name "Net-(LED29-DOUT)") (class "Default")
      (node (ref "LED29") (pin "2") (pinfunction "DOUT_2") (pintype "passive"))
      (node (ref "LED30") (pin "4") (pinfunction "DIN_4") (pintype "passive"))
    )
    (net (code "30") (name "Net-(LED31-DOUT)") (class "Default")
      (node (ref "LED31") (pin "2") (pinfunction "DOUT_2") (pintype "passive"))
      (node (ref "LED32") (pin "4") (pinfunction "DIN_4") (pintype "passive"))
    )
    (net (code "31") (name "Net-(LED32-DOUT)") (class "Default")
      (node (ref "LED32") (pin "2") (pinfunction "DOUT_2") (pintype "passive"))
      (node (ref "LED33") (pin "4") (pinfunction "DIN_4") (pintype "passive"))
    )
    (net (code "32") (name "Net-(LED33-DOUT)") (class "Default")
      (node (ref "LED33") (pin "2") (pinfunction "DOUT_2") (pintype "passive"))
      (node (ref "LED34") (pin "4") (pinfunction "DIN_4") (pintype "passive"))
    )
    (net (code "33") (name "Net-(LED34-DOUT)") (class "Default")
      (node (ref "LED34") (pin "2") (pinfunction "DOUT_2") (pintype "passive"))
      (node (ref "LED35") (pin "4") (pinfunction "DIN_4") (pintype "passive"))
    )
    (net (code "34") (name "Net-(LED35-DOUT)") (class "Default")
      (node (ref "LED35") (pin "2") (pinfunction "DOUT_2") (pintype "passive"))
      (node (ref "LED36") (pin "4") (pinfunction "DIN_4") (pintype "passive"))
    )
    (net (code "35") (name "Net-(LED36-DOUT)") (class "Default")
      (node (ref "LED36") (pin "2") (pinfunction "DOUT_2") (pintype "passive"))
      (node (ref "LED37") (pin "4") (pinfunction "DIN_4") (pintype "passive"))
    )
    (net (code "36") (name "Net-(LED37-DOUT)") (class "Default")
      (node (ref "LED37") (pin "2") (pinfunction "DOUT_2") (pintype "passive"))
      (node (ref "LED38") (pin "4") (pinfunction "DIN_4") (pintype "passive"))
    )
    (net (code "37") (name "Net-(LED38-DOUT)") (class "Default")
      (node (ref "LED38") (pin "2") (pinfunction "DOUT_2") (pintype "passive"))
      (node (ref "LED39") (pin "4") (pinfunction "DIN_4") (pintype "passive"))
    )
    (net (code "38") (name "Net-(LED39-DOUT)") (class "Default")
      (node (ref "LED39") (pin "2") (pinfunction "DOUT_2") (pintype "passive"))
      (node (ref "LED40") (pin "4") (pinfunction "DIN_4") (pintype "passive"))
    )
    (net (code "39") (name "Net-(LED41-DOUT)") (class "Default")
      (node (ref "LED41") (pin "2") (pinfunction "DOUT_2") (pintype "passive"))
      (node (ref "LED42") (pin "4") (pinfunction "DIN_4") (pintype "passive"))
    )
    (net (code "40") (name "Net-(LED42-DOUT)") (class "Default")
      (node (ref "LED42") (pin "2") (pinfunction "DOUT_2") (pintype "passive"))
      (node (ref "LED43") (pin "4") (pinfunction "DIN_4") (pintype "passive"))
    )
    (net (code "41") (name "Net-(LED43-DOUT)") (class "Default")
      (node (ref "LED43") (pin "2") (pinfunction "DOUT_2") (pintype "passive"))
      (node (ref "LED44") (pin "4") (pinfunction "DIN_4") (pintype "passive"))
    )
    (net (code "42") (name "Net-(LED44-DOUT)") (class "Default")
      (node (ref "LED44") (pin "2") (pinfunction "DOUT_2") (pintype "passive"))
      (node (ref "LED45") (pin "4") (pinfunction "DIN_4") (pintype "passive"))
    )
    (net (code "43") (name "Net-(LED45-DOUT)") (class "Default")
      (node (ref "LED45") (pin "2") (pinfunction "DOUT_2") (pintype "passive"))
      (node (ref "LED46") (pin "4") (pinfunction "DIN_4") (pintype "passive"))
    )
    (net (code "44") (name "Net-(LED46-DOUT)") (class "Default")
      (node (ref "LED46") (pin "2") (pinfunction "DOUT_2") (pintype "passive"))
      (node (ref "LED47") (pin "4") (pinfunction "DIN_4") (pintype "passive"))
    )
    (net (code "45") (name "Net-(LED47-DOUT)") (class "Default")
      (node (ref "LED47") (pin "2") (pinfunction "DOUT_2") (pintype "passive"))
      (node (ref "LED48") (pin "4") (pinfunction "DIN_4") (pintype "passive"))
    )
    (net (code "46") (name "Net-(LED48-DOUT)") (class "Default")
      (node (ref "LED48") (pin "2") (pinfunction "DOUT_2") (pintype "passive"))
      (node (ref "LED49") (pin "4") (pinfunction "DIN_4") (pintype "passive"))
    )
    (net (code "47") (name "Net-(LED49-DOUT)") (class "Default")
      (node (ref "LED49") (pin "2") (pinfunction "DOUT_2") (pintype "passive"))
      (node (ref "LED50") (pin "4") (pinfunction "DIN_4") (pintype "passive"))
    )
    (net (code "48") (name "Net-(LED51-DOUT)") (class "Default")
      (node (ref "LED51") (pin "2") (pinfunction "DOUT_2") (pintype "passive"))
      (node (ref "LED52") (pin "4") (pinfunction "DIN_4") (pintype "passive"))
    )
    (net (code "49") (name "Net-(LED52-DOUT)") (class "Default")
      (node (ref "LED52") (pin "2") (pinfunction "DOUT_2") (pintype "passive"))
      (node (ref "LED53") (pin "4") (pinfunction "DIN_4") (pintype "passive"))
    )
    (net (code "50") (name "Net-(LED53-DOUT)") (class "Default")
      (node (ref "LED53") (pin "2") (pinfunction "DOUT_2") (pintype "passive"))
      (node (ref "LED54") (pin "4") (pinfunction "DIN_4") (pintype "passive"))
    )
    (net (code "51") (name "Net-(LED54-DOUT)") (class "Default")
      (node (ref "LED54") (pin "2") (pinfunction "DOUT_2") (pintype "passive"))
      (node (ref "LED55") (pin "4") (pinfunction "DIN_4") (pintype "passive"))
    )
    (net (code "52") (name "Net-(LED55-DOUT)") (class "Default")
      (node (ref "LED55") (pin "2") (pinfunction "DOUT_2") (pintype "passive"))
      (node (ref "LED56") (pin "4") (pinfunction "DIN_4") (pintype "passive"))
    )
    (net (code "53") (name "Net-(LED56-DOUT)") (class "Default")
      (node (ref "LED56") (pin "2") (pinfunction "DOUT_2") (pintype "passive"))
      (node (ref "LED57") (pin "4") (pinfunction "DIN_4") (pintype "passive"))
    )
    (net (code "54") (name "Net-(LED57-DOUT)") (class "Default")
      (node (ref "LED57") (pin "2") (pinfunction "DOUT_2") (pintype "passive"))
      (node (ref "LED58") (pin "4") (pinfunction "DIN_4") (pintype "passive"))
    )
    (net (code "55") (name "Net-(LED58-DOUT)") (class "Default")
      (node (ref "LED58") (pin "2") (pinfunction "DOUT_2") (pintype "passive"))
      (node (ref "LED59") (pin "4") (pinfunction "DIN_4") (pintype "passive"))
    )
    (net (code "56") (name "Net-(LED59-DOUT)") (class "Default")
      (node (ref "LED59") (pin "2") (pinfunction "DOUT_2") (pintype "passive"))
      (node (ref "LED60") (pin "4") (pinfunction "DIN_4") (pintype "passive"))
    )
    (net (code "57") (name "Net-(LED61-DOUT)") (class "Default")
      (node (ref "LED61") (pin "2") (pinfunction "DOUT_2") (pintype "passive"))
      (node (ref "LED62") (pin "4") (pinfunction "DIN_4") (pintype "passive"))
    )
    (net (code "58") (name "Net-(LED62-DOUT)") (class "Default")
      (node (ref "LED62") (pin "2") (pinfunction "DOUT_2") (pintype "passive"))
      (node (ref "LED63") (pin "4") (pinfunction "DIN_4") (pintype "passive"))
    )
    (net (code "59") (name "Net-(LED63-DOUT)") (class "Default")
      (node (ref "LED63") (pin "2") (pinfunction "DOUT_2") (pintype "passive"))
      (node (ref "LED64") (pin "4") (pinfunction "DIN_4") (pintype "passive"))
    )
    (net (code "60") (name "Net-(LED64-DOUT)") (class "Default")
      (node (ref "LED64") (pin "2") (pinfunction "DOUT_2") (pintype "passive"))
      (node (ref "LED65") (pin "4") (pinfunction "DIN_4") (pintype "passive"))
    )
    (net (code "61") (name "Net-(LED65-DOUT)") (class "Default")
      (node (ref "LED65") (pin "2") (pinfunction "DOUT_2") (pintype "passive"))
      (node (ref "LED66") (pin "4") (pinfunction "DIN_4") (pintype "passive"))
    )
    (net (code "62") (name "Net-(LED66-DOUT)") (class "Default")
      (node (ref "LED66") (pin "2") (pinfunction "DOUT_2") (pintype "passive"))
      (node (ref "LED67") (pin "4") (pinfunction "DIN_4") (pintype "passive"))
    )
    (net (code "63") (name "Net-(LED67-DOUT)") (class "Default")
      (node (ref "LED67") (pin "2") (pinfunction "DOUT_2") (pintype "passive"))
      (node (ref "LED68") (pin "4") (pinfunction "DIN_4") (pintype "passive"))
    )
    (net (code "64") (name "Net-(LED68-DOUT)") (class "Default")
      (node (ref "LED68") (pin "2") (pinfunction "DOUT_2") (pintype "passive"))
      (node (ref "LED69") (pin "4") (pinfunction "DIN_4") (pintype "passive"))
    )
    (net (code "65") (name "Net-(LED69-DOUT)") (class "Default")
      (node (ref "LED69") (pin "2") (pinfunction "DOUT_2") (pintype "passive"))
      (node (ref "LED70") (pin "4") (pinfunction "DIN_4") (pintype "passive"))
    )
    (net (code "66") (name "Net-(LED71-DOUT)") (class "Default")
      (node (ref "LED71") (pin "2") (pinfunction "DOUT_2") (pintype "passive"))
      (node (ref "LED72") (pin "4") (pinfunction "DIN_4") (pintype "passive"))
    )
    (net (code "67") (name "Net-(LED72-DOUT)") (class "Default")
      (node (ref "LED72") (pin "2") (pinfunction "DOUT_2") (pintype "passive"))
      (node (ref "LED73") (pin "4") (pinfunction "DIN_4") (pintype "passive"))
    )
    (net (code "68") (name "Net-(LED73-DOUT)") (class "Default")
      (node (ref "LED73") (pin "2") (pinfunction "DOUT_2") (pintype "passive"))
      (node (ref "LED74") (pin "4") (pinfunction "DIN_4") (pintype "passive"))
    )
    (net (code "69") (name "Net-(U4-Y)") (class "Default")
      (node (ref "R9") (pin "2") (pinfunction "2_2") (pintype "passive"))
      (node (ref "U4") (pin "4") (pinfunction "Y_4") (pintype "passive"))
    )
    (net (code "70") (name "unconnected-(LED74-DOUT-Pad2)") (class "Default")
      (node (ref "LED74") (pin "2") (pinfunction "DOUT_2") (pintype "passive+no_connect"))
    )
  )
)
